# PSE_project.net
KiCad netlist of a schematic drawn in EAGLE
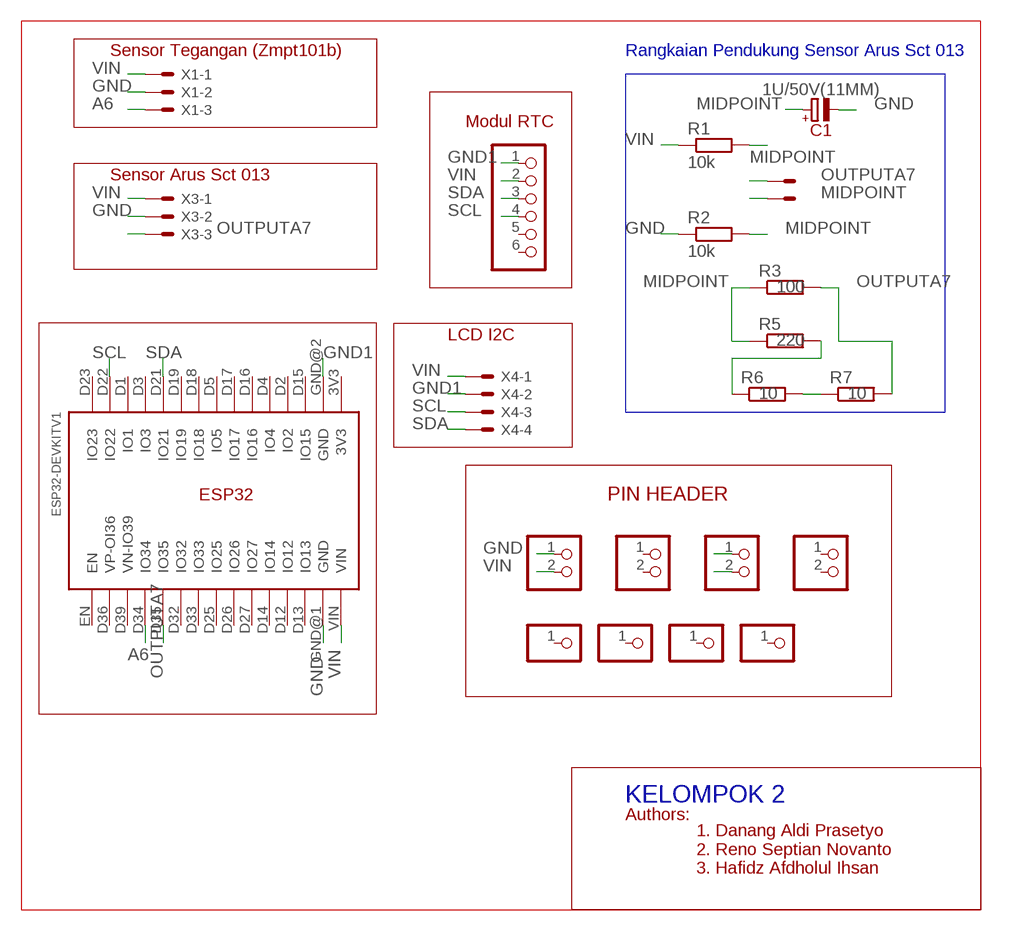
[diagram p0: schematic, sheet 1]

(export (version "E")
  (design (tool "Eeschema 10.0.6"))
  (components
    (comp (ref "C1")
      (value "1U/50V(11MM)")
      (footprint "eagle-import:E2-5")
      (libsource (lib "eagle-import") (part "?1U/50V(11MM)"))
    )
    (comp (ref "JP1")
      (value "PINHD-1X2")
      (footprint "eagle-import:1X02")
      (libsource (lib "eagle-import") (part "PINHD-1X2"))
    )
    (comp (ref "JP2")
      (value "PINHD-1X2")
      (footprint "eagle-import:1X02")
      (libsource (lib "eagle-import") (part "PINHD-1X2"))
    )
    (comp (ref "JP3")
      (value "PINHD-1X2")
      (footprint "eagle-import:1X02")
      (libsource (lib "eagle-import") (part "PINHD-1X2"))
    )
    (comp (ref "JP4")
      (value "PINHD-1X2")
      (footprint "eagle-import:1X02")
      (libsource (lib "eagle-import") (part "PINHD-1X2"))
    )
    (comp (ref "JP5")
      (value "PINHD-1X6")
      (footprint "eagle-import:1X06")
      (libsource (lib "eagle-import") (part "PINHD-1X6"))
    )
    (comp (ref "JP6")
      (value "PINHD-1X1")
      (footprint "eagle-import:1X01")
      (libsource (lib "eagle-import") (part "PINHD-1X1"))
    )
    (comp (ref "JP7")
      (value "PINHD-1X1")
      (footprint "eagle-import:1X01")
      (libsource (lib "eagle-import") (part "PINHD-1X1"))
    )
    (comp (ref "JP8")
      (value "PINHD-1X1")
      (footprint "eagle-import:1X01")
      (libsource (lib "eagle-import") (part "PINHD-1X1"))
    )
    (comp (ref "JP9")
      (value "PINHD-1X1")
      (footprint "eagle-import:1X01")
      (libsource (lib "eagle-import") (part "PINHD-1X1"))
    )
    (comp (ref "R1")
      (value "10k")
      (footprint "eagle-import:0204_5")
      (libsource (lib "eagle-import") (part "R-EU_0204/5"))
    )
    (comp (ref "R2")
      (value "10k")
      (footprint "eagle-import:0204_5")
      (libsource (lib "eagle-import") (part "R-EU_0204/5"))
    )
    (comp (ref "R3")
      (value "100")
      (footprint "eagle-import:0204_5")
      (libsource (lib "eagle-import") (part "R-EU_0204/5"))
    )
    (comp (ref "R5")
      (value "220")
      (footprint "eagle-import:0204_5")
      (libsource (lib "eagle-import") (part "R-EU_0204/5"))
    )
    (comp (ref "R6")
      (value "10")
      (footprint "eagle-import:0204_5")
      (libsource (lib "eagle-import") (part "R-EU_0204/5"))
    )
    (comp (ref "R7")
      (value "10")
      (footprint "eagle-import:0204_5")
      (libsource (lib "eagle-import") (part "R-EU_0204/5"))
    )
    (comp (ref "U$1")
      (value "ESP32DEVKITV1")
      (footprint "eagle-import:ESP32-DEVKITV1")
      (libsource (lib "eagle-import") (part "ESP32DEVKITV1"))
    )
    (comp (ref "X1")
      (value "JST-XH-03-PIN-LONG-PAD")
      (footprint "eagle-import:JST-XH-03-PACKAGE-LONG-PAD")
      (libsource (lib "eagle-import") (part "JST-XH-03-PIN-LONG-PAD"))
    )
    (comp (ref "X3")
      (value "JST-XH-03-PIN-LONG-PAD")
      (footprint "eagle-import:JST-XH-03-PACKAGE-LONG-PAD")
      (libsource (lib "eagle-import") (part "JST-XH-03-PIN-LONG-PAD"))
    )
    (comp (ref "X4")
      (value "JST-XH-04-PIN-LONG-PAD")
      (footprint "eagle-import:JST-XH-04-PACKAGE-LONG-PAD")
      (libsource (lib "eagle-import") (part "JST-XH-04-PIN-LONG-PAD"))
    )
    (comp (ref "X7")
      (value "JST-XH-02-PIN-LONG-PAD")
      (footprint "eagle-import:JST-XH-02-PACKAGE-LONG-PAD")
      (libsource (lib "eagle-import") (part "JST-XH-02-PIN-LONG-PAD"))
    )
  )
  (nets
    (net (code "1") (name "/A6") (class "Default")
      (node (ref "U$1") (pin "D34") (pinfunction "IO34_D34") (pintype "bidirectional"))
      (node (ref "X1") (pin "3") (pinfunction "S_3") (pintype "passive"))
    )
    (net (code "2") (name "/GND") (class "Default")
      (node (ref "C1") (pin "-") (pinfunction "-_-") (pintype "passive"))
      (node (ref "JP1") (pin "1") (pinfunction "1_1") (pintype "passive"))
      (node (ref "R2") (pin "1") (pinfunction "1_1") (pintype "passive"))
      (node (ref "U$1") (pin "GND@1") (pinfunction "GND_GND@1") (pintype "bidirectional"))
      (node (ref "X1") (pin "2") (pinfunction "S_2") (pintype "passive"))
      (node (ref "X3") (pin "2") (pinfunction "S_2") (pintype "passive"))
    )
    (net (code "3") (name "/GND1") (class "Default")
      (node (ref "JP5") (pin "1") (pinfunction "1_1") (pintype "passive"))
      (node (ref "U$1") (pin "GND@2") (pinfunction "GND_GND@2") (pintype "bidirectional"))
      (node (ref "X4") (pin "2") (pinfunction "S_2") (pintype "passive"))
    )
    (net (code "4") (name "/MIDPOINT") (class "Default")
      (node (ref "C1") (pin "+") (pinfunction "+_+") (pintype "passive"))
      (node (ref "R1") (pin "2") (pinfunction "2_2") (pintype "passive"))
      (node (ref "R2") (pin "2") (pinfunction "2_2") (pintype "passive"))
      (node (ref "R3") (pin "1") (pinfunction "1_1") (pintype "passive"))
      (node (ref "R5") (pin "1") (pinfunction "1_1") (pintype "passive"))
      (node (ref "X7") (pin "2") (pinfunction "S_2") (pintype "passive"))
    )
    (net (code "5") (name "/OUTPUTA7") (class "Default")
      (node (ref "R3") (pin "2") (pinfunction "2_2") (pintype "passive"))
      (node (ref "R7") (pin "2") (pinfunction "2_2") (pintype "passive"))
      (node (ref "U$1") (pin "D35") (pinfunction "IO35_D35") (pintype "bidirectional"))
      (node (ref "X3") (pin "3") (pinfunction "S_3") (pintype "passive"))
      (node (ref "X7") (pin "1") (pinfunction "S_1") (pintype "passive"))
    )
    (net (code "6") (name "/SCL") (class "Default")
      (node (ref "JP5") (pin "4") (pinfunction "4_4") (pintype "passive"))
      (node (ref "U$1") (pin "D22") (pinfunction "IO22_D22") (pintype "bidirectional"))
      (node (ref "X4") (pin "3") (pinfunction "S_3") (pintype "passive"))
    )
    (net (code "7") (name "/SDA") (class "Default")
      (node (ref "JP5") (pin "3") (pinfunction "3_3") (pintype "passive"))
      (node (ref "U$1") (pin "D21") (pinfunction "IO21_D21") (pintype "bidirectional"))
      (node (ref "X4") (pin "4") (pinfunction "S_4") (pintype "passive"))
    )
    (net (code "8") (name "/VIN") (class "Default")
      (node (ref "JP1") (pin "2") (pinfunction "2_2") (pintype "passive"))
      (node (ref "JP5") (pin "2") (pinfunction "2_2") (pintype "passive"))
      (node (ref "R1") (pin "1") (pinfunction "1_1") (pintype "passive"))
      (node (ref "U$1") (pin "VIN") (pinfunction "VIN_VIN") (pintype "bidirectional"))
      (node (ref "X1") (pin "1") (pinfunction "S_1") (pintype "passive"))
      (node (ref "X3") (pin "1") (pinfunction "S_1") (pintype "passive"))
      (node (ref "X4") (pin "1") (pinfunction "S_1") (pintype "passive"))
    )
    (net (code "9") (name "Net-(R5-Pad2)") (class "Default")
      (node (ref "R5") (pin "2") (pinfunction "2_2") (pintype "passive"))
      (node (ref "R6") (pin "1") (pinfunction "1_1") (pintype "passive"))
    )
    (net (code "10") (name "Net-(R6-Pad2)") (class "Default")
      (node (ref "R6") (pin "2") (pinfunction "2_2") (pintype "passive"))
      (node (ref "R7") (pin "1") (pinfunction "1_1") (pintype "passive"))
    )
    (net (code "11") (name "unconnected-(JP2-Pad1)") (class "Default")
      (node (ref "JP2") (pin "1") (pinfunction "1_1") (pintype "passive"))
    )
    (net (code "12") (name "unconnected-(JP2-Pad2)") (class "Default")
      (node (ref "JP2") (pin "2") (pinfunction "2_2") (pintype "passive"))
    )
    (net (code "13") (name "unconnected-(JP3-Pad1)") (class "Default")
      (node (ref "JP3") (pin "1") (pinfunction "1_1") (pintype "passive"))
    )
    (net (code "14") (name "unconnected-(JP3-Pad2)") (class "Default")
      (node (ref "JP3") (pin "2") (pinfunction "2_2") (pintype "passive"))
    )
    (net (code "15") (name "unconnected-(JP4-Pad1)") (class "Default")
      (node (ref "JP4") (pin "1") (pinfunction "1_1") (pintype "passive"))
    )
    (net (code "16") (name "unconnected-(JP4-Pad2)") (class "Default")
      (node (ref "JP4") (pin "2") (pinfunction "2_2") (pintype "passive"))
    )
    (net (code "17") (name "unconnected-(JP5-Pad5)") (class "Default")
      (node (ref "JP5") (pin "5") (pinfunction "5_5") (pintype "passive"))
    )
    (net (code "18") (name "unconnected-(JP5-Pad6)") (class "Default")
      (node (ref "JP5") (pin "6") (pinfunction "6_6") (pintype "passive"))
    )
    (net (code "19") (name "unconnected-(JP6-Pad1)") (class "Default")
      (node (ref "JP6") (pin "1") (pinfunction "1_1") (pintype "passive"))
    )
    (net (code "20") (name "unconnected-(JP7-Pad1)") (class "Default")
      (node (ref "JP7") (pin "1") (pinfunction "1_1") (pintype "passive"))
    )
    (net (code "21") (name "unconnected-(JP8-Pad1)") (class "Default")
      (node (ref "JP8") (pin "1") (pinfunction "1_1") (pintype "passive"))
    )
    (net (code "22") (name "unconnected-(JP9-Pad1)") (class "Default")
      (node (ref "JP9") (pin "1") (pinfunction "1_1") (pintype "passive"))
    )
    (net (code "23") (name "unconnected-(U$1-IO1-PadD1)") (class "Default")
      (node (ref "U$1") (pin "D1") (pinfunction "IO1_D1") (pintype "bidirectional"))
    )
    (net (code "24") (name "unconnected-(U$1-IO2-PadD2)") (class "Default")
      (node (ref "U$1") (pin "D2") (pinfunction "IO2_D2") (pintype "bidirectional"))
    )
    (net (code "25") (name "unconnected-(U$1-IO3-PadD3)") (class "Default")
      (node (ref "U$1") (pin "D3") (pinfunction "IO3_D3") (pintype "bidirectional"))
    )
    (net (code "26") (name "unconnected-(U$1-IO4-PadD4)") (class "Default")
      (node (ref "U$1") (pin "D4") (pinfunction "IO4_D4") (pintype "bidirectional"))
    )
    (net (code "27") (name "unconnected-(U$1-IO5-PadD5)") (class "Default")
      (node (ref "U$1") (pin "D5") (pinfunction "IO5_D5") (pintype "bidirectional"))
    )
    (net (code "28") (name "unconnected-(U$1-IO12-PadD12)") (class "Default")
      (node (ref "U$1") (pin "D12") (pinfunction "IO12_D12") (pintype "bidirectional"))
    )
    (net (code "29") (name "unconnected-(U$1-IO13-PadD13)") (class "Default")
      (node (ref "U$1") (pin "D13") (pinfunction "IO13_D13") (pintype "bidirectional"))
    )
    (net (code "30") (name "unconnected-(U$1-IO14-PadD14)") (class "Default")
      (node (ref "U$1") (pin "D14") (pinfunction "IO14_D14") (pintype "bidirectional"))
    )
    (net (code "31") (name "unconnected-(U$1-IO15-PadD15)") (class "Default")
      (node (ref "U$1") (pin "D15") (pinfunction "IO15_D15") (pintype "bidirectional"))
    )
    (net (code "32") (name "unconnected-(U$1-IO16-PadD16)") (class "Default")
      (node (ref "U$1") (pin "D16") (pinfunction "IO16_D16") (pintype "bidirectional"))
    )
    (net (code "33") (name "unconnected-(U$1-IO17-PadD17)") (class "Default")
      (node (ref "U$1") (pin "D17") (pinfunction "IO17_D17") (pintype "bidirectional"))
    )
    (net (code "34") (name "unconnected-(U$1-IO18-PadD18)") (class "Default")
      (node (ref "U$1") (pin "D18") (pinfunction "IO18_D18") (pintype "bidirectional"))
    )
    (net (code "35") (name "unconnected-(U$1-IO19-PadD19)") (class "Default")
      (node (ref "U$1") (pin "D19") (pinfunction "IO19_D19") (pintype "bidirectional"))
    )
    (net (code "36") (name "unconnected-(U$1-IO23-PadD23)") (class "Default")
      (node (ref "U$1") (pin "D23") (pinfunction "IO23_D23") (pintype "bidirectional"))
    )
    (net (code "37") (name "unconnected-(U$1-IO25-PadD25)") (class "Default")
      (node (ref "U$1") (pin "D25") (pinfunction "IO25_D25") (pintype "bidirectional"))
    )
    (net (code "38") (name "unconnected-(U$1-IO26-PadD26)") (class "Default")
      (node (ref "U$1") (pin "D26") (pinfunction "IO26_D26") (pintype "bidirectional"))
    )
    (net (code "39") (name "unconnected-(U$1-IO27-PadD27)") (class "Default")
      (node (ref "U$1") (pin "D27") (pinfunction "IO27_D27") (pintype "bidirectional"))
    )
    (net (code "40") (name "unconnected-(U$1-IO32-PadD32)") (class "Default")
      (node (ref "U$1") (pin "D32") (pinfunction "IO32_D32") (pintype "bidirectional"))
    )
    (net (code "41") (name "unconnected-(U$1-IO33-PadD33)") (class "Default")
      (node (ref "U$1") (pin "D33") (pinfunction "IO33_D33") (pintype "bidirectional"))
    )
    (net (code "42") (name "unconnected-(U$1-Pad3V3)") (class "Default")
      (node (ref "U$1") (pin "3V3") (pinfunction "3V3_3V3") (pintype "bidirectional"))
    )
    (net (code "43") (name "unconnected-(U$1-PadEN)") (class "Default")
      (node (ref "U$1") (pin "EN") (pinfunction "EN_EN") (pintype "bidirectional"))
    )
    (net (code "44") (name "unconnected-(U$1-VN-IO39-PadD39)") (class "Default")
      (node (ref "U$1") (pin "D39") (pinfunction "VN-IO39_D39") (pintype "bidirectional"))
    )
    (net (code "45") (name "unconnected-(U$1-VP-OI36-PadD36)") (class "Default")
      (node (ref "U$1") (pin "D36") (pinfunction "VP-OI36_D36") (pintype "bidirectional"))
    )
  )
)
